# ziffy_board_v4.net
KiCad netlist of a schematic drawn in EAGLE
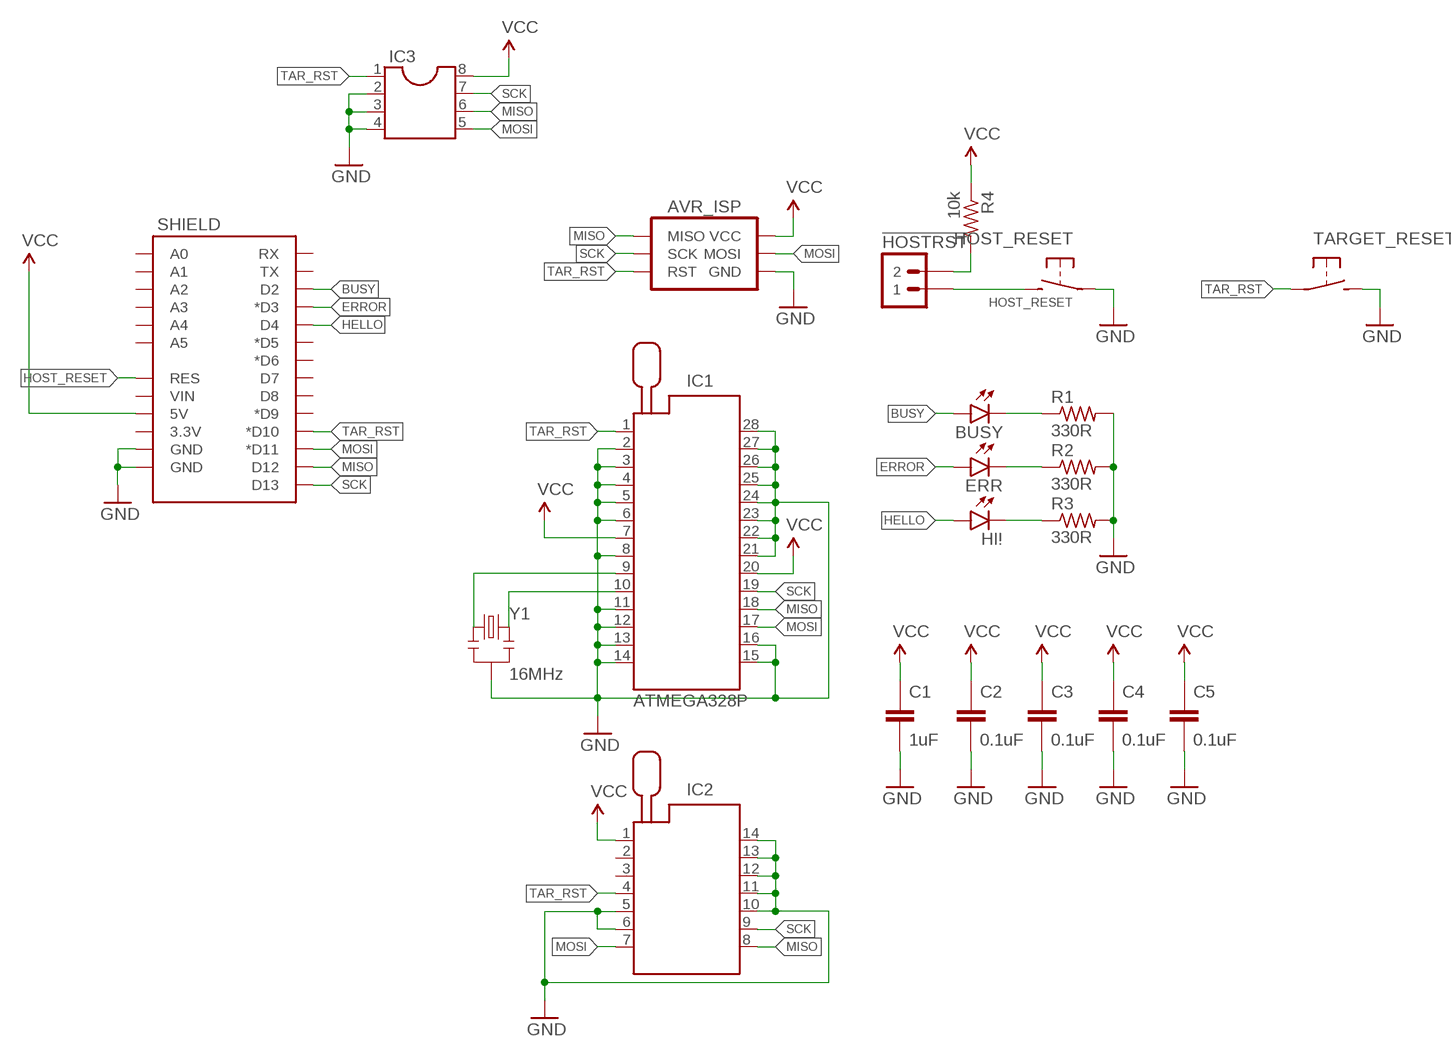
[diagram p0: schematic, sheet 1]

(export (version "E")
  (design (tool "Eeschema 10.0.6"))
  (components
    (comp (ref "!HOSTRST")
      (value "M02PTH")
      (footprint "eagle-import:1X02")
      (libsource (lib "eagle-import") (part "M02PTH"))
    )
    (comp (ref "AVR_ISP")
      (value "AVR_SPI_PRG_6PTH-SHROUD")
      (footprint "eagle-import:2X3-SHROUDED")
      (libsource (lib "eagle-import") (part "AVR_SPI_PRG_6PTH-SHROUD"))
    )
    (comp (ref "BUSY")
      (value "YELLOW")
      (footprint "eagle-import:LED3MM")
      (libsource (lib "eagle-import") (part "LED3MM"))
    )
    (comp (ref "C1")
      (value "1uF")
      (footprint "eagle-import:C025-024X044")
      (libsource (lib "eagle-import") (part "CAPACITOR-CERAMIC025-024X044"))
    )
    (comp (ref "C2")
      (value "0.1uF")
      (footprint "eagle-import:C025-024X044")
      (libsource (lib "eagle-import") (part "CAPACITOR-CERAMIC025-024X044"))
    )
    (comp (ref "C3")
      (value "0.1uF")
      (footprint "eagle-import:C025-024X044")
      (libsource (lib "eagle-import") (part "CAPACITOR-CERAMIC025-024X044"))
    )
    (comp (ref "C4")
      (value "0.1uF")
      (footprint "eagle-import:C025-024X044")
      (libsource (lib "eagle-import") (part "CAPACITOR-CERAMIC025-024X044"))
    )
    (comp (ref "C5")
      (value "0.1uF")
      (footprint "eagle-import:C025-024X044")
      (libsource (lib "eagle-import") (part "CAPACITOR-CERAMIC025-024X044"))
    )
    (comp (ref "ERR")
      (value "RED")
      (footprint "eagle-import:LED3MM")
      (libsource (lib "eagle-import") (part "LED3MM"))
    )
    (comp (ref "HI!")
      (value "GREEN")
      (footprint "eagle-import:LED3MM")
      (libsource (lib "eagle-import") (part "LED3MM"))
    )
    (comp (ref "HOST_RESET")
      (value "SPST-NO-TACT3MM-PTH-SMALL-PADS")
      (footprint "eagle-import:DTS-3-SMALL-PADS")
      (libsource (lib "eagle-import") (part "SPST-NO-TACT3MM-PTH-SMALL-PADS"))
    )
    (comp (ref "IC1")
      (value "ATMEGA328P")
      (footprint "eagle-import:ZIF28")
      (libsource (lib "eagle-import") (part "ZIF28"))
    )
    (comp (ref "IC2")
      (value "ATTINY84")
      (footprint "eagle-import:ZIF14")
      (fields (field (name "MF") "3M") (field (name "MPN") "214-3339-00-0602J"))
      (libsource (lib "eagle-import") (part "ZIF14"))
    )
    (comp (ref "IC3")
      (value "DIL8")
      (footprint "eagle-import:DIL08")
      (libsource (lib "eagle-import") (part "DIL8"))
    )
    (comp (ref "R1")
      (value "330R")
      (footprint "eagle-import:RESISTOR-AXIAL-PTH-6.35MM")
      (libsource (lib "eagle-import") (part "RESISTORPTH-AXIAL-6.35MM"))
    )
    (comp (ref "R2")
      (value "330R")
      (footprint "eagle-import:RESISTOR-AXIAL-PTH-6.35MM")
      (libsource (lib "eagle-import") (part "RESISTORPTH-AXIAL-6.35MM"))
    )
    (comp (ref "R3")
      (value "330R")
      (footprint "eagle-import:RESISTOR-AXIAL-PTH-6.35MM")
      (libsource (lib "eagle-import") (part "RESISTORPTH-AXIAL-6.35MM"))
    )
    (comp (ref "R4")
      (value "10k")
      (footprint "eagle-import:RESISTOR-AXIAL-PTH-5.08MM")
      (libsource (lib "eagle-import") (part "RESISTORPTH-AXIAL-5.08MM"))
    )
    (comp (ref "SHIELD")
      (value "ARDUINO_SHIELD_SMALLER")
      (footprint "eagle-import:ARDUINO_SHIELD_NOOUTLINE_INSIDE_SMALLER")
      (libsource (lib "eagle-import") (part "ARDUINO_SHIELD_SMALLER"))
    )
    (comp (ref "TARGET_RESET")
      (value "SPST-NO-TACT3MM-PTH-SMALL-PADS")
      (footprint "eagle-import:DTS-3-SMALL-PADS")
      (libsource (lib "eagle-import") (part "SPST-NO-TACT3MM-PTH-SMALL-PADS"))
    )
    (comp (ref "Y1")
      (value "16MHz")
      (footprint "eagle-import:RESONATOR-PTH")
      (libsource (lib "eagle-import") (part "RESONATORPTH"))
    )
  )
  (nets
    (net (code "1") (name "BUSY") (class "Default")
      (node (ref "BUSY") (pin "A") (pinfunction "A_A") (pintype "passive"))
      (node (ref "SHIELD") (pin "D2") (pinfunction "D2_D2") (pintype "bidirectional"))
    )
    (net (code "2") (name "ERROR") (class "Default")
      (node (ref "ERR") (pin "A") (pinfunction "A_A") (pintype "passive"))
      (node (ref "SHIELD") (pin "D3") (pinfunction "*D3_D3") (pintype "bidirectional"))
    )
    (net (code "3") (name "GND") (class "Default")
      (node (ref "AVR_ISP") (pin "6") (pinfunction "GND_6") (pintype "passive"))
      (node (ref "C1") (pin "2") (pinfunction "2_2") (pintype "passive"))
      (node (ref "C2") (pin "2") (pinfunction "2_2") (pintype "passive"))
      (node (ref "C3") (pin "2") (pinfunction "2_2") (pintype "passive"))
      (node (ref "C4") (pin "2") (pinfunction "2_2") (pintype "passive"))
      (node (ref "C5") (pin "2") (pinfunction "2_2") (pintype "passive"))
      (node (ref "HOST_RESET") (pin "1") (pinfunction "1_1") (pintype "passive"))
      (node (ref "IC1") (pin "11") (pinfunction "11_11") (pintype "passive"))
      (node (ref "IC1") (pin "12") (pinfunction "12_12") (pintype "passive"))
      (node (ref "IC1") (pin "13") (pinfunction "13_13") (pintype "passive"))
      (node (ref "IC1") (pin "14") (pinfunction "14_14") (pintype "passive"))
      (node (ref "IC1") (pin "15") (pinfunction "15_15") (pintype "passive"))
      (node (ref "IC1") (pin "16") (pinfunction "16_16") (pintype "passive"))
      (node (ref "IC1") (pin "2") (pinfunction "2_2") (pintype "passive"))
      (node (ref "IC1") (pin "21") (pinfunction "21_21") (pintype "passive"))
      (node (ref "IC1") (pin "22") (pinfunction "22_22") (pintype "passive"))
      (node (ref "IC1") (pin "23") (pinfunction "23_23") (pintype "passive"))
      (node (ref "IC1") (pin "24") (pinfunction "24_24") (pintype "passive"))
      (node (ref "IC1") (pin "25") (pinfunction "25_25") (pintype "passive"))
      (node (ref "IC1") (pin "26") (pinfunction "26_26") (pintype "passive"))
      (node (ref "IC1") (pin "27") (pinfunction "27_27") (pintype "passive"))
      (node (ref "IC1") (pin "28") (pinfunction "28_28") (pintype "passive"))
      (node (ref "IC1") (pin "3") (pinfunction "3_3") (pintype "passive"))
      (node (ref "IC1") (pin "4") (pinfunction "4_4") (pintype "passive"))
      (node (ref "IC1") (pin "5") (pinfunction "5_5") (pintype "passive"))
      (node (ref "IC1") (pin "6") (pinfunction "6_6") (pintype "passive"))
      (node (ref "IC1") (pin "8") (pinfunction "8_8") (pintype "passive"))
      (node (ref "IC2") (pin "10") (pinfunction "10_10") (pintype "passive"))
      (node (ref "IC2") (pin "11") (pinfunction "11_11") (pintype "passive"))
      (node (ref "IC2") (pin "12") (pinfunction "12_12") (pintype "passive"))
      (node (ref "IC2") (pin "13") (pinfunction "13_13") (pintype "passive"))
      (node (ref "IC2") (pin "14") (pinfunction "14_14") (pintype "passive"))
      (node (ref "IC2") (pin "5") (pinfunction "5_5") (pintype "passive"))
      (node (ref "IC2") (pin "6") (pinfunction "6_6") (pintype "passive"))
      (node (ref "IC3") (pin "2") (pinfunction "2_2") (pintype "passive"))
      (node (ref "IC3") (pin "3") (pinfunction "3_3") (pintype "passive"))
      (node (ref "IC3") (pin "4") (pinfunction "4_4") (pintype "passive"))
      (node (ref "R1") (pin "P$2") (pinfunction "2_P$2") (pintype "passive"))
      (node (ref "R2") (pin "P$2") (pinfunction "2_P$2") (pintype "passive"))
      (node (ref "R3") (pin "P$2") (pinfunction "2_P$2") (pintype "passive"))
      (node (ref "SHIELD") (pin "GND@0") (pinfunction "GND_GND@0") (pintype "bidirectional"))
      (node (ref "SHIELD") (pin "GND@1") (pinfunction "GND_GND@1") (pintype "bidirectional"))
      (node (ref "TARGET_RESET") (pin "2") (pinfunction "2_2") (pintype "passive"))
      (node (ref "Y1") (pin "2") (pinfunction "2_2") (pintype "passive"))
    )
    (net (code "4") (name "HELLO") (class "Default")
      (node (ref "HI!") (pin "A") (pinfunction "A_A") (pintype "passive"))
      (node (ref "SHIELD") (pin "D4") (pinfunction "D4_D4") (pintype "bidirectional"))
    )
    (net (code "5") (name "HOST_RESET") (class "Default")
      (node (ref "!HOSTRST") (pin "1") (pinfunction "1_1") (pintype "passive"))
      (node (ref "HOST_RESET") (pin "2") (pinfunction "2_2") (pintype "passive"))
      (node (ref "SHIELD") (pin "RES") (pinfunction "RES_RES") (pintype "bidirectional"))
    )
    (net (code "6") (name "MISO") (class "Default")
      (node (ref "AVR_ISP") (pin "1") (pinfunction "MISO_1") (pintype "passive"))
      (node (ref "IC1") (pin "18") (pinfunction "18_18") (pintype "passive"))
      (node (ref "IC2") (pin "8") (pinfunction "8_8") (pintype "passive"))
      (node (ref "IC3") (pin "6") (pinfunction "6_6") (pintype "passive"))
      (node (ref "SHIELD") (pin "D12") (pinfunction "D12_D12") (pintype "bidirectional"))
    )
    (net (code "7") (name "MOSI") (class "Default")
      (node (ref "AVR_ISP") (pin "4") (pinfunction "MOSI_4") (pintype "passive"))
      (node (ref "IC1") (pin "17") (pinfunction "17_17") (pintype "passive"))
      (node (ref "IC2") (pin "7") (pinfunction "7_7") (pintype "passive"))
      (node (ref "IC3") (pin "5") (pinfunction "5_5") (pintype "passive"))
      (node (ref "SHIELD") (pin "D11") (pinfunction "*D11_D11") (pintype "bidirectional"))
    )
    (net (code "8") (name "Net-(BUSY-C)") (class "Default")
      (node (ref "BUSY") (pin "K") (pinfunction "C_K") (pintype "passive"))
      (node (ref "R1") (pin "P$1") (pinfunction "1_P$1") (pintype "passive"))
    )
    (net (code "9") (name "Net-(ERR-C)") (class "Default")
      (node (ref "ERR") (pin "K") (pinfunction "C_K") (pintype "passive"))
      (node (ref "R2") (pin "P$1") (pinfunction "1_P$1") (pintype "passive"))
    )
    (net (code "10") (name "Net-(HI!-C)") (class "Default")
      (node (ref "HI!") (pin "K") (pinfunction "C_K") (pintype "passive"))
      (node (ref "R3") (pin "P$1") (pinfunction "1_P$1") (pintype "passive"))
    )
    (net (code "11") (name "Net-(IC1-Pad9)") (class "Default")
      (node (ref "IC1") (pin "9") (pinfunction "9_9") (pintype "passive"))
      (node (ref "Y1") (pin "1") (pinfunction "1_1") (pintype "passive"))
    )
    (net (code "12") (name "Net-(IC1-Pad10)") (class "Default")
      (node (ref "IC1") (pin "10") (pinfunction "10_10") (pintype "passive"))
      (node (ref "Y1") (pin "3") (pinfunction "3_3") (pintype "passive"))
    )
    (net (code "13") (name "Net-(R4-2)") (class "Default")
      (node (ref "!HOSTRST") (pin "2") (pinfunction "2_2") (pintype "passive"))
      (node (ref "R4") (pin "P$2") (pinfunction "2_P$2") (pintype "passive"))
    )
    (net (code "14") (name "SCK") (class "Default")
      (node (ref "AVR_ISP") (pin "3") (pinfunction "SCK_3") (pintype "passive"))
      (node (ref "IC1") (pin "19") (pinfunction "19_19") (pintype "passive"))
      (node (ref "IC2") (pin "9") (pinfunction "9_9") (pintype "passive"))
      (node (ref "IC3") (pin "7") (pinfunction "7_7") (pintype "passive"))
      (node (ref "SHIELD") (pin "D13") (pinfunction "D13_D13") (pintype "bidirectional"))
    )
    (net (code "15") (name "TAR_RST") (class "Default")
      (node (ref "AVR_ISP") (pin "5") (pinfunction "RST_5") (pintype "passive"))
      (node (ref "IC1") (pin "1") (pinfunction "1_1") (pintype "passive"))
      (node (ref "IC2") (pin "4") (pinfunction "4_4") (pintype "passive"))
      (node (ref "IC3") (pin "1") (pinfunction "1_1") (pintype "passive"))
      (node (ref "SHIELD") (pin "D10") (pinfunction "*D10_D10") (pintype "bidirectional"))
      (node (ref "TARGET_RESET") (pin "1") (pinfunction "1_1") (pintype "passive"))
    )
    (net (code "16") (name "VCC") (class "Default")
      (node (ref "AVR_ISP") (pin "2") (pinfunction "VCC_2") (pintype "passive"))
      (node (ref "C1") (pin "1") (pinfunction "1_1") (pintype "passive"))
      (node (ref "C2") (pin "1") (pinfunction "1_1") (pintype "passive"))
      (node (ref "C3") (pin "1") (pinfunction "1_1") (pintype "passive"))
      (node (ref "C4") (pin "1") (pinfunction "1_1") (pintype "passive"))
      (node (ref "C5") (pin "1") (pinfunction "1_1") (pintype "passive"))
      (node (ref "IC1") (pin "20") (pinfunction "20_20") (pintype "passive"))
      (node (ref "IC1") (pin "7") (pinfunction "7_7") (pintype "passive"))
      (node (ref "IC2") (pin "1") (pinfunction "1_1") (pintype "passive"))
      (node (ref "IC3") (pin "8") (pinfunction "8_8") (pintype "passive"))
      (node (ref "R4") (pin "P$1") (pinfunction "1_P$1") (pintype "passive"))
      (node (ref "SHIELD") (pin "5V") (pinfunction "5V_5V") (pintype "bidirectional"))
    )
    (net (code "17") (name "unconnected-(IC2-Pad2)") (class "Default")
      (node (ref "IC2") (pin "2") (pinfunction "2_2") (pintype "passive"))
    )
    (net (code "18") (name "unconnected-(IC2-Pad3)") (class "Default")
      (node (ref "IC2") (pin "3") (pinfunction "3_3") (pintype "passive"))
    )
    (net (code "19") (name "unconnected-(SHIELD-*D5-PadD5)") (class "Default")
      (node (ref "SHIELD") (pin "D5") (pinfunction "*D5_D5") (pintype "bidirectional"))
    )
    (net (code "20") (name "unconnected-(SHIELD-*D6-PadD6)") (class "Default")
      (node (ref "SHIELD") (pin "D6") (pinfunction "*D6_D6") (pintype "bidirectional"))
    )
    (net (code "21") (name "unconnected-(SHIELD-*D9-PadD9)") (class "Default")
      (node (ref "SHIELD") (pin "D9") (pinfunction "*D9_D9") (pintype "bidirectional"))
    )
    (net (code "22") (name "unconnected-(SHIELD-Pad3.3V)") (class "Default")
      (node (ref "SHIELD") (pin "3.3V") (pinfunction "3.3V_3.3V") (pintype "bidirectional"))
    )
    (net (code "23") (name "unconnected-(SHIELD-PadA0)") (class "Default")
      (node (ref "SHIELD") (pin "A0") (pinfunction "A0_A0") (pintype "bidirectional"))
    )
    (net (code "24") (name "unconnected-(SHIELD-PadA1)") (class "Default")
      (node (ref "SHIELD") (pin "A1") (pinfunction "A1_A1") (pintype "bidirectional"))
    )
    (net (code "25") (name "unconnected-(SHIELD-PadA2)") (class "Default")
      (node (ref "SHIELD") (pin "A2") (pinfunction "A2_A2") (pintype "bidirectional"))
    )
    (net (code "26") (name "unconnected-(SHIELD-PadA3)") (class "Default")
      (node (ref "SHIELD") (pin "A3") (pinfunction "A3_A3") (pintype "bidirectional"))
    )
    (net (code "27") (name "unconnected-(SHIELD-PadA4)") (class "Default")
      (node (ref "SHIELD") (pin "A4") (pinfunction "A4_A4") (pintype "bidirectional"))
    )
    (net (code "28") (name "unconnected-(SHIELD-PadA5)") (class "Default")
      (node (ref "SHIELD") (pin "A5") (pinfunction "A5_A5") (pintype "bidirectional"))
    )
    (net (code "29") (name "unconnected-(SHIELD-PadD7)") (class "Default")
      (node (ref "SHIELD") (pin "D7") (pinfunction "D7_D7") (pintype "bidirectional"))
    )
    (net (code "30") (name "unconnected-(SHIELD-PadD8)") (class "Default")
      (node (ref "SHIELD") (pin "D8") (pinfunction "D8_D8") (pintype "bidirectional"))
    )
    (net (code "31") (name "unconnected-(SHIELD-PadRX)") (class "Default")
      (node (ref "SHIELD") (pin "RX") (pinfunction "RX_RX") (pintype "bidirectional"))
    )
    (net (code "32") (name "unconnected-(SHIELD-PadTX)") (class "Default")
      (node (ref "SHIELD") (pin "TX") (pinfunction "TX_TX") (pintype "bidirectional"))
    )
    (net (code "33") (name "unconnected-(SHIELD-PadVIN)") (class "Default")
      (node (ref "SHIELD") (pin "VIN") (pinfunction "VIN_VIN") (pintype "bidirectional"))
    )
  )
)
